# PIC32ETH_Peripheral.net
KiCad netlist of a schematic drawn in Altium Designer
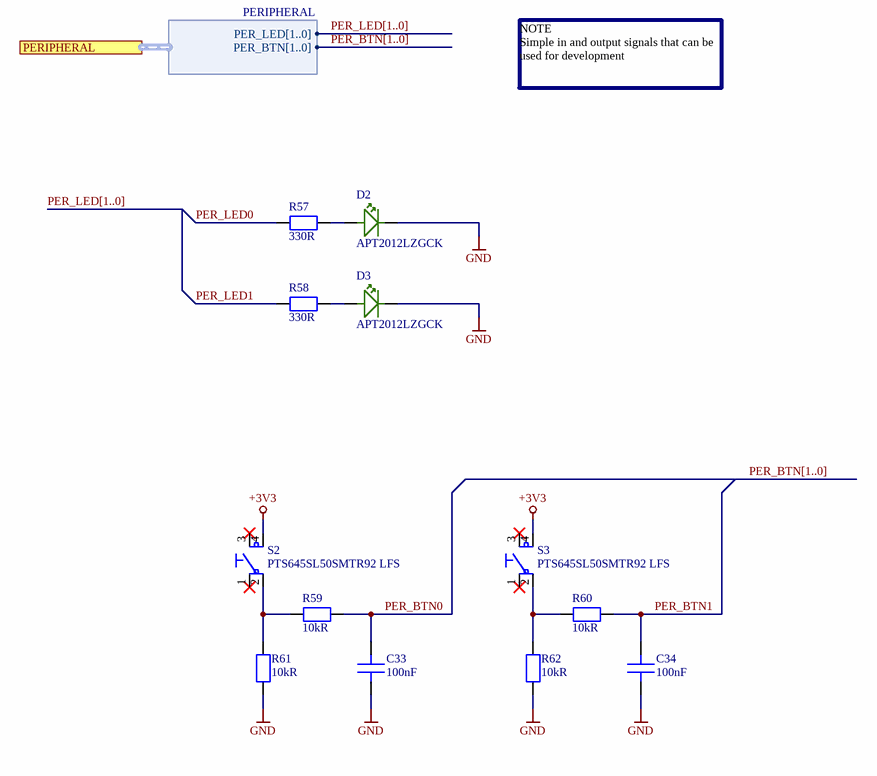
[diagram p0: PIC32ETH_Peripheral.SchDoc]

(export (version "E")
  (design (tool "Eeschema 10.0.6"))
  (components
    (comp (ref "C33")
      (value "100nF")
      (footprint "C_CHIP2012N")
      (description "C CERAMIC 100nF 50V 10% 2012")
      (fields (field (name "MANUFACTURER") "Kemet") (field (name "PART NUMBER") "C0805C104K5RACTU"))
      (libsource (lib "PIC32ETH") (part "C_C0805C104K5RACTU"))
    )
    (comp (ref "C34")
      (value "100nF")
      (footprint "C_CHIP2012N")
      (description "C CERAMIC 100nF 50V 10% 2012")
      (fields (field (name "MANUFACTURER") "Kemet") (field (name "PART NUMBER") "C0805C104K5RACTU"))
      (libsource (lib "PIC32ETH") (part "C_C0805C104K5RACTU"))
    )
    (comp (ref "D2")
      (value "APT2012LZGCK")
      (footprint "D_LEDCHIP2012N")
      (description "D LED GREEN CLEAR 2.65V 2mA 2012")
      (fields (field (name "MANUFACTURER") "Kingbright") (field (name "POWER") "102.5mW"))
      (libsource (lib "PIC32ETH") (part "D_APT2012LZGCK"))
    )
    (comp (ref "D3")
      (value "APT2012LZGCK")
      (footprint "D_LEDCHIP2012N")
      (description "D LED GREEN CLEAR 2.65V 2mA 2012")
      (fields (field (name "MANUFACTURER") "Kingbright") (field (name "POWER") "102.5mW"))
      (libsource (lib "PIC32ETH") (part "D_APT2012LZGCK"))
    )
    (comp (ref "R57")
      (value "330R")
      (footprint "R_CHIP2012N")
      (description "R SMT 330R 1% 125mW 2012")
      (fields
        (field (name "MANUFACTURER") "Stackpole Electronics Inc")
        (field (name "PART NUMBER") "RMCF0805FT330R")
      )
      (libsource (lib "PIC32ETH") (part "R_RMCF0805FT330R"))
    )
    (comp (ref "R58")
      (value "330R")
      (footprint "R_CHIP2012N")
      (description "R SMT 330R 1% 125mW 2012")
      (fields
        (field (name "MANUFACTURER") "Stackpole Electronics Inc")
        (field (name "PART NUMBER") "RMCF0805FT330R")
      )
      (libsource (lib "PIC32ETH") (part "R_RMCF0805FT330R"))
    )
    (comp (ref "R59")
      (value "10kR")
      (footprint "R_CHIP2012N")
      (description "R SMT 10kR 1% 125mW 2012")
      (fields
        (field (name "MANUFACTURER") "Stackpole Electronics Inc")
        (field (name "PART NUMBER") "RMCF0805FT10K0")
      )
      (libsource (lib "PIC32ETH") (part "R_RMCF0805FT10K0"))
    )
    (comp (ref "R60")
      (value "10kR")
      (footprint "R_CHIP2012N")
      (description "R SMT 10kR 1% 125mW 2012")
      (fields
        (field (name "MANUFACTURER") "Stackpole Electronics Inc")
        (field (name "PART NUMBER") "RMCF0805FT10K0")
      )
      (libsource (lib "PIC32ETH") (part "R_RMCF0805FT10K0"))
    )
    (comp (ref "R61")
      (value "10kR")
      (footprint "R_CHIP2012N")
      (description "R SMT 10kR 1% 125mW 2012")
      (fields
        (field (name "MANUFACTURER") "Stackpole Electronics Inc")
        (field (name "PART NUMBER") "RMCF0805FT10K0")
      )
      (libsource (lib "PIC32ETH") (part "R_RMCF0805FT10K0"))
    )
    (comp (ref "R62")
      (value "10kR")
      (footprint "R_CHIP2012N")
      (description "R SMT 10kR 1% 125mW 2012")
      (fields
        (field (name "MANUFACTURER") "Stackpole Electronics Inc")
        (field (name "PART NUMBER") "RMCF0805FT10K0")
      )
      (libsource (lib "PIC32ETH") (part "R_RMCF0805FT10K0"))
    )
    (comp (ref "S2")
      (value "PTS645SL50SMTR92 LFS")
      (footprint "S_CHIPP620X620-4N")
      (description "S TACTILE SPST-NO 12V 50mA SMT")
      (fields (field (name "MANUFACTURER") "C&K") (field (name "VOLTAGE") "12V"))
      (libsource (lib "PIC32ETH") (part "S_PTS645SL50SMTR92LFS"))
    )
    (comp (ref "S3")
      (value "PTS645SL50SMTR92 LFS")
      (footprint "S_CHIPP620X620-4N")
      (description "S TACTILE SPST-NO 12V 50mA SMT")
      (fields (field (name "MANUFACTURER") "C&K") (field (name "VOLTAGE") "12V"))
      (libsource (lib "PIC32ETH") (part "S_PTS645SL50SMTR92LFS"))
    )
  )
  (nets
    (net (code "2") (name "+3V3") (class "Default")
      (node (ref "S2") (pin "4") (pinfunction "4_4") (pintype "passive"))
      (node (ref "S3") (pin "4") (pinfunction "4_4") (pintype "passive"))
    )
    (net (code "4") (name "/PER_BTN0") (class "Default")
      (node (ref "C33") (pin "1") (pinfunction "1_1") (pintype "passive"))
      (node (ref "R59") (pin "1") (pinfunction "1_1") (pintype "passive"))
    )
    (net (code "5") (name "/PER_BTN1") (class "Default")
      (node (ref "C34") (pin "1") (pinfunction "1_1") (pintype "passive"))
      (node (ref "R60") (pin "1") (pinfunction "1_1") (pintype "passive"))
    )
    (net (code "7") (name "/PER_LED0") (class "Default")
      (node (ref "R57") (pin "1") (pinfunction "1_1") (pintype "passive"))
    )
    (net (code "8") (name "/PER_LED1") (class "Default")
      (node (ref "R58") (pin "1") (pinfunction "1_1") (pintype "passive"))
    )
    (net (code "10") (name "GND") (class "Default")
      (node (ref "C33") (pin "2") (pinfunction "2_2") (pintype "passive"))
      (node (ref "C34") (pin "2") (pinfunction "2_2") (pintype "passive"))
      (node (ref "D2") (pin "1") (pinfunction "1_1") (pintype "passive"))
      (node (ref "D3") (pin "1") (pinfunction "1_1") (pintype "passive"))
      (node (ref "R61") (pin "1") (pinfunction "1_1") (pintype "passive"))
      (node (ref "R62") (pin "1") (pinfunction "1_1") (pintype "passive"))
    )
    (net (code "11") (name "Net-(D2-Pad2)") (class "Default")
      (node (ref "D2") (pin "2") (pinfunction "2_2") (pintype "passive"))
      (node (ref "R57") (pin "2") (pinfunction "2_2") (pintype "passive"))
    )
    (net (code "12") (name "Net-(D3-Pad2)") (class "Default")
      (node (ref "D3") (pin "2") (pinfunction "2_2") (pintype "passive"))
      (node (ref "R58") (pin "2") (pinfunction "2_2") (pintype "passive"))
    )
    (net (code "13") (name "Net-(R59-Pad2)") (class "Default")
      (node (ref "R59") (pin "2") (pinfunction "2_2") (pintype "passive"))
      (node (ref "R61") (pin "2") (pinfunction "2_2") (pintype "passive"))
      (node (ref "S2") (pin "2") (pinfunction "2_2") (pintype "passive"))
    )
    (net (code "14") (name "Net-(R60-Pad2)") (class "Default")
      (node (ref "R60") (pin "2") (pinfunction "2_2") (pintype "passive"))
      (node (ref "R62") (pin "2") (pinfunction "2_2") (pintype "passive"))
      (node (ref "S3") (pin "2") (pinfunction "2_2") (pintype "passive"))
    )
    (net (code "15") (name "unconnected-(S2-Pad1)") (class "Default")
      (node (ref "S2") (pin "1") (pinfunction "1_1") (pintype "passive+no_connect"))
    )
    (net (code "16") (name "unconnected-(S2-Pad3)") (class "Default")
      (node (ref "S2") (pin "3") (pinfunction "3_3") (pintype "passive+no_connect"))
    )
    (net (code "17") (name "unconnected-(S3-Pad1)") (class "Default")
      (node (ref "S3") (pin "1") (pinfunction "1_1") (pintype "passive+no_connect"))
    )
    (net (code "18") (name "unconnected-(S3-Pad3)") (class "Default")
      (node (ref "S3") (pin "3") (pinfunction "3_3") (pintype "passive+no_connect"))
    )
  )
)
